# 12V_Buck_Converter.net
KiCad netlist of a schematic drawn in Altium Designer
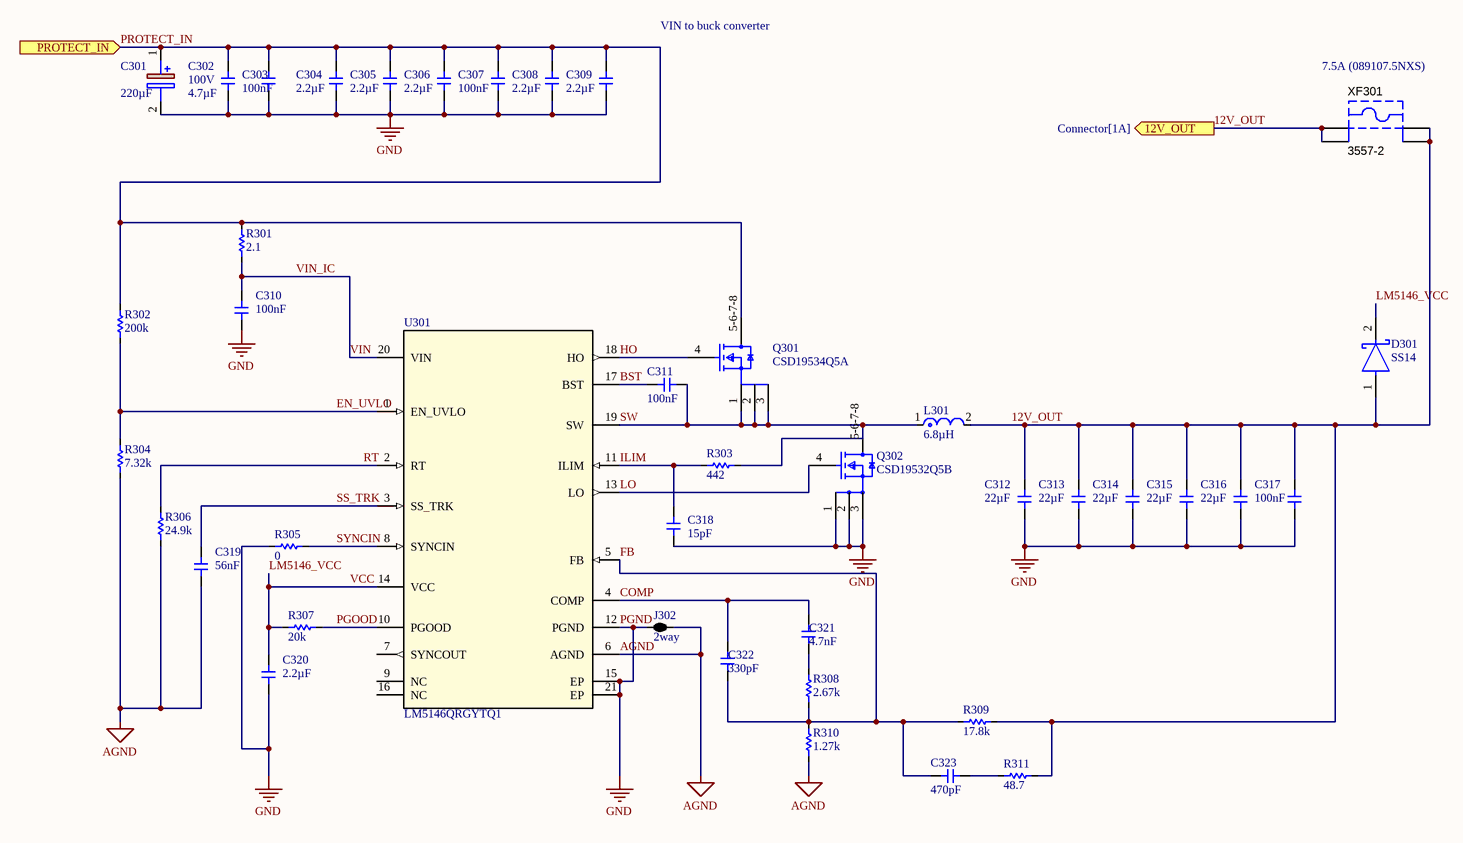
[diagram p0: 12V_Buck_Converter.SchDoc]

(export (version "E")
  (design (tool "Eeschema 10.0.6"))
  (components
    (comp (ref "C301")
      (value "220µF")
      (footprint "SamacSys:EEEFK0J103SM")
      (description "Capacitor Polarised")
      (fields
        (field (name "MANUFACTURER_PART_NUMBER") "EEV-FK2A221M")
        (field (name "MOUSER PART NUMBER") "667-EEV-FK2A221M")
      )
      (libsource (lib "*") (part "EEV-FK2A221M"))
    )
    (comp (ref "C302")
      (value "non-polar_Capacitor")
      (footprint "1210")
      (description "SMD type ceramic capacitor")
      (fields
        (field (name "VOLTAGE") "100V")
        (field (name "CAPACITANCE") "4.7µF")
        (field (name "SOURCE") "robit_passive.SchLib")
      )
      (libsource (lib "robit circuit") (part "Capacitor"))
    )
    (comp (ref "C303")
      (value "non-polar_Capacitor")
      (footprint "0603")
      (description "SMD type ceramic capacitor")
      (fields
        (field (name "VOLTAGE") "100V")
        (field (name "CAPACITANCE") "100nF")
        (field (name "SOURCE") "robit_passive.SchLib")
      )
      (libsource (lib "robit circuit") (part "Capacitor"))
    )
    (comp (ref "C304")
      (value "non-polar_Capacitor")
      (footprint "1210")
      (description "SMD type ceramic capacitor")
      (fields
        (field (name "VOLTAGE") "50V")
        (field (name "CAPACITANCE") "2.2µF")
        (field (name "SOURCE") "robit_passive.SchLib")
      )
      (libsource (lib "robit circuit") (part "Capacitor"))
    )
    (comp (ref "C305")
      (value "non-polar_Capacitor")
      (footprint "1210")
      (description "SMD type ceramic capacitor")
      (fields
        (field (name "VOLTAGE") "50V")
        (field (name "CAPACITANCE") "2.2µF")
        (field (name "SOURCE") "robit_passive.SchLib")
      )
      (libsource (lib "robit circuit") (part "Capacitor"))
    )
    (comp (ref "C306")
      (value "non-polar_Capacitor")
      (footprint "0603")
      (description "SMD type ceramic capacitor")
      (fields
        (field (name "VOLTAGE") "50V")
        (field (name "CAPACITANCE") "2.2µF")
        (field (name "SOURCE") "robit_passive.SchLib")
      )
      (libsource (lib "robit circuit") (part "Capacitor"))
    )
    (comp (ref "C307")
      (value "non-polar_Capacitor")
      (footprint "0603")
      (description "SMD type ceramic capacitor")
      (fields
        (field (name "VOLTAGE") "50V")
        (field (name "CAPACITANCE") "100nF")
        (field (name "SOURCE") "robit_passive.SchLib")
      )
      (libsource (lib "robit circuit") (part "Capacitor"))
    )
    (comp (ref "C308")
      (value "non-polar_Capacitor")
      (footprint "1210")
      (description "SMD type ceramic capacitor")
      (fields
        (field (name "VOLTAGE") "50V")
        (field (name "CAPACITANCE") "2.2µF")
        (field (name "SOURCE") "robit_passive.SchLib")
      )
      (libsource (lib "robit circuit") (part "Capacitor"))
    )
    (comp (ref "C309")
      (value "non-polar_Capacitor")
      (footprint "1210")
      (description "SMD type ceramic capacitor")
      (fields
        (field (name "VOLTAGE") "50V")
        (field (name "CAPACITANCE") "2.2µF")
        (field (name "SOURCE") "robit_passive.SchLib")
      )
      (libsource (lib "robit circuit") (part "Capacitor"))
    )
    (comp (ref "C310")
      (value "non-polar_Capacitor")
      (footprint "0603")
      (description "SMD type ceramic capacitor")
      (fields
        (field (name "VOLTAGE") "50V")
        (field (name "CAPACITANCE") "100nF")
        (field (name "SOURCE") "robit_passive.SchLib")
      )
      (libsource (lib "robit circuit") (part "Capacitor"))
    )
    (comp (ref "C311")
      (value "non-polar_Capacitor")
      (footprint "0603")
      (description "SMD type ceramic capacitor")
      (fields
        (field (name "VOLTAGE") "50V")
        (field (name "CAPACITANCE") "100nF")
        (field (name "SOURCE") "robit_passive.SchLib")
      )
      (libsource (lib "robit circuit") (part "Capacitor"))
    )
    (comp (ref "C312")
      (value "non-polar_Capacitor")
      (footprint "1210")
      (description "SMD type ceramic capacitor")
      (fields
        (field (name "VOLTAGE") "50V")
        (field (name "CAPACITANCE") "22µF")
        (field (name "SOURCE") "robit_passive.SchLib")
      )
      (libsource (lib "robit circuit") (part "Capacitor"))
    )
    (comp (ref "C313")
      (value "non-polar_Capacitor")
      (footprint "1210")
      (description "SMD type ceramic capacitor")
      (fields
        (field (name "VOLTAGE") "50V")
        (field (name "CAPACITANCE") "22µF")
        (field (name "SOURCE") "robit_passive.SchLib")
      )
      (libsource (lib "robit circuit") (part "Capacitor"))
    )
    (comp (ref "C314")
      (value "non-polar_Capacitor")
      (footprint "1210")
      (description "SMD type ceramic capacitor")
      (fields
        (field (name "VOLTAGE") "50V")
        (field (name "CAPACITANCE") "22µF")
        (field (name "SOURCE") "robit_passive.SchLib")
      )
      (libsource (lib "robit circuit") (part "Capacitor"))
    )
    (comp (ref "C315")
      (value "non-polar_Capacitor")
      (footprint "1210")
      (description "SMD type ceramic capacitor")
      (fields
        (field (name "VOLTAGE") "50V")
        (field (name "CAPACITANCE") "22µF")
        (field (name "SOURCE") "robit_passive.SchLib")
      )
      (libsource (lib "robit circuit") (part "Capacitor"))
    )
    (comp (ref "C316")
      (value "non-polar_Capacitor")
      (footprint "1210")
      (description "SMD type ceramic capacitor")
      (fields
        (field (name "VOLTAGE") "50V")
        (field (name "CAPACITANCE") "22µF")
        (field (name "SOURCE") "robit_passive.SchLib")
      )
      (libsource (lib "robit circuit") (part "Capacitor"))
    )
    (comp (ref "C317")
      (value "non-polar_Capacitor")
      (footprint "0603")
      (description "SMD type ceramic capacitor")
      (fields
        (field (name "VOLTAGE") "100V")
        (field (name "CAPACITANCE") "100nF")
        (field (name "SOURCE") "robit_passive.SchLib")
      )
      (libsource (lib "robit circuit") (part "Capacitor"))
    )
    (comp (ref "C318")
      (value "non-polar_Capacitor")
      (footprint "0603")
      (description "SMD type ceramic capacitor")
      (fields
        (field (name "VOLTAGE") "50V")
        (field (name "CAPACITANCE") "15pF")
        (field (name "SOURCE") "robit_passive.SchLib")
      )
      (libsource (lib "robit circuit") (part "Capacitor"))
    )
    (comp (ref "C319")
      (value "non-polar_Capacitor")
      (footprint "0603")
      (description "SMD type ceramic capacitor")
      (fields
        (field (name "VOLTAGE") "50V")
        (field (name "CAPACITANCE") "56nF")
        (field (name "SOURCE") "robit_passive.SchLib")
      )
      (libsource (lib "robit circuit") (part "Capacitor"))
    )
    (comp (ref "C320")
      (value "non-polar_Capacitor")
      (footprint "1206")
      (description "SMD type ceramic capacitor")
      (fields
        (field (name "VOLTAGE") "50V")
        (field (name "CAPACITANCE") "2.2µF")
        (field (name "SOURCE") "robit_passive.SchLib")
      )
      (libsource (lib "robit circuit") (part "Capacitor"))
    )
    (comp (ref "C321")
      (value "non-polar_Capacitor")
      (footprint "0603")
      (description "SMD type ceramic capacitor")
      (fields
        (field (name "VOLTAGE") "50V")
        (field (name "CAPACITANCE") "4.7nF")
        (field (name "SOURCE") "robit_passive.SchLib")
      )
      (libsource (lib "robit circuit") (part "Capacitor"))
    )
    (comp (ref "C322")
      (value "non-polar_Capacitor")
      (footprint "0603")
      (description "SMD type ceramic capacitor")
      (fields
        (field (name "VOLTAGE") "50V")
        (field (name "CAPACITANCE") "330pF")
        (field (name "SOURCE") "robit_passive.SchLib")
      )
      (libsource (lib "robit circuit") (part "Capacitor"))
    )
    (comp (ref "C323")
      (value "non-polar_Capacitor")
      (footprint "0603")
      (description "SMD type ceramic capacitor")
      (fields
        (field (name "VOLTAGE") "50V")
        (field (name "CAPACITANCE") "470pF")
        (field (name "SOURCE") "robit_passive.SchLib")
      )
      (libsource (lib "robit circuit") (part "Capacitor"))
    )
    (comp (ref "D301")
      (value "SS14")
      (footprint "FP-403AE-MFG")
      (description "DIODE SCHOTTKY 40V 1A SMA")
      (fields
        (field (name "MANUFACTURER") "ON Semiconductor")
        (field (name "OCTOPART") "https://octopart.com/ss14-on+semiconductor-29205033")
      )
      (libsource (lib "Altium Content Vault") (part "360ad2f4ac25a952324d13796385471"))
    )
    (comp (ref "J302")
      (value "2way")
      (footprint "2way_LP")
      (description "2 way net tie junction")
      (libsource (lib "robit circuit") (part "2way"))
    )
    (comp (ref "L301")
      (value "XAL1010")
      (footprint "FP-XAL1010-MFG")
      (description "General Purpose Inductor, 5.6uH, 20%, 1 Element, Composite-Core, SMD, 4539")
      (fields (field (name "INDUCTANCE") "6.8µH"))
      (libsource (lib "robit circuit") (part "4cc4b267dca4c8e51f7102f422741d8"))
    )
    (comp (ref "Q301")
      (value "CSD19534Q5A")
      (footprint "FP-DQJ0008A-MFG")
      (description "MOSFET N-CH 100V 50 8SON")
      (fields
        (field (name "OCTOPART") "https://octopart.com/csd19534q5a-texas+instruments-46749514")
        (field (name "MANUFACTURER") "Texas Instruments")
      )
      (libsource (lib "Altium Content Vault") (part "372bcbff2a0099001efc4acc0eb9b45"))
    )
    (comp (ref "Q302")
      (value "CSD19532Q5B")
      (footprint "FP-DNK0008A-MFG")
      (description "100-V, N channel NexFET™ power MOSFET, single SON 5 mm x 6 mm, 4.9 mOhm 8-VSON-CLIP -55 to 150")
      (libsource (lib "robit circuit") (part "6fb2c024a3b9031f6d89538bc87a0fd"))
    )
    (comp (ref "R301")
      (value "Resistor")
      (footprint "0603")
      (description "SMD type resistor")
      (fields (field (name "RESISTANCE") "2.1") (field (name "SOURCE") "robit_passive.SchLib"))
      (libsource (lib "robit circuit") (part "Resistor"))
    )
    (comp (ref "R302")
      (value "Resistor")
      (footprint "0603")
      (description "SMD type resistor")
      (fields (field (name "RESISTANCE") "200k") (field (name "SOURCE") "robit_passive.SchLib"))
      (libsource (lib "robit circuit") (part "Resistor"))
    )
    (comp (ref "R303")
      (value "Resistor")
      (footprint "0805")
      (description "SMD type resistor")
      (fields (field (name "RESISTANCE") "442") (field (name "SOURCE") "robit_passive.SchLib"))
      (libsource (lib "robit circuit") (part "Resistor"))
    )
    (comp (ref "R304")
      (value "Resistor")
      (footprint "0603")
      (description "SMD type resistor")
      (fields (field (name "RESISTANCE") "7.32k") (field (name "SOURCE") "robit_passive.SchLib"))
      (libsource (lib "robit circuit") (part "Resistor"))
    )
    (comp (ref "R305")
      (value "Resistor")
      (footprint "0603")
      (description "SMD type resistor")
      (fields (field (name "RESISTANCE") "0") (field (name "SOURCE") "robit_passive.SchLib"))
      (libsource (lib "robit circuit") (part "Resistor"))
    )
    (comp (ref "R306")
      (value "Resistor")
      (footprint "0603")
      (description "SMD type resistor")
      (fields (field (name "RESISTANCE") "24.9k") (field (name "SOURCE") "robit_passive.SchLib"))
      (libsource (lib "robit circuit") (part "Resistor"))
    )
    (comp (ref "R307")
      (value "Resistor")
      (footprint "0603")
      (description "SMD type resistor")
      (fields (field (name "RESISTANCE") "20k") (field (name "SOURCE") "robit_passive.SchLib"))
      (libsource (lib "robit circuit") (part "Resistor"))
    )
    (comp (ref "R308")
      (value "Resistor")
      (footprint "0603")
      (description "SMD type resistor")
      (fields (field (name "RESISTANCE") "2.67k") (field (name "SOURCE") "robit_passive.SchLib"))
      (libsource (lib "robit circuit") (part "Resistor"))
    )
    (comp (ref "R309")
      (value "Resistor")
      (footprint "0603")
      (description "SMD type resistor")
      (fields (field (name "RESISTANCE") "17.8k") (field (name "SOURCE") "robit_passive.SchLib"))
      (libsource (lib "robit circuit") (part "Resistor"))
    )
    (comp (ref "R310")
      (value "Resistor")
      (footprint "0603")
      (description "SMD type resistor")
      (fields (field (name "RESISTANCE") "1.27k") (field (name "SOURCE") "robit_passive.SchLib"))
      (libsource (lib "robit circuit") (part "Resistor"))
    )
    (comp (ref "R311")
      (value "Resistor")
      (footprint "0603")
      (description "SMD type resistor")
      (fields (field (name "RESISTANCE") "48.7") (field (name "SOURCE") "robit_passive.SchLib"))
      (libsource (lib "robit circuit") (part "Resistor"))
    )
    (comp (ref "U301")
      (value "LM5146QRGYTQ1")
      (footprint "RGY0020B")
      (description "Automotive 100-V synchronous buck DC/DC controller with wide duty-cycle range 20-VQFN -40 to 150")
      (fields (field (name "COPYRIGHT") "Copyright (C) 2026 Ultra Librarian. All rights reserved."))
      (libsource (lib "LM5146QRGYTQ1") (part "LM5146QRGYTQ1"))
    )
    (comp (ref "XF301")
      (value "3557-2")
      (footprint "KSTN-3557-2")
      (description "FUSE HOLDER, PCB MOUNT, 500VAC, 20A, ROHS")
      (fields (field (name "VOLTAGE") "500V") (field (name "MANUFACTURER") "Keystone-Electronics"))
      (libsource (lib "Altium Content Vault") (part "FUSE_HOLDER-4"))
    )
  )
  (nets
    (net (code "1") (name "/12V_OUT") (class "Default")
      (node (ref "C312") (pin "2") (pinfunction "2_2") (pintype "passive"))
      (node (ref "C313") (pin "2") (pinfunction "2_2") (pintype "passive"))
      (node (ref "C314") (pin "2") (pinfunction "2_2") (pintype "passive"))
      (node (ref "C315") (pin "2") (pinfunction "2_2") (pintype "passive"))
      (node (ref "C316") (pin "2") (pinfunction "2_2") (pintype "passive"))
      (node (ref "C317") (pin "2") (pinfunction "2_2") (pintype "passive"))
      (node (ref "D301") (pin "1") (pinfunction "A_1") (pintype "passive"))
      (node (ref "L301") (pin "2") (pinfunction "2_2") (pintype "passive"))
      (node (ref "R309") (pin "1") (pinfunction "1_1") (pintype "passive"))
      (node (ref "R311") (pin "1") (pinfunction "1_1") (pintype "passive"))
      (node (ref "XF301") (pin "1") (pinfunction "1_1") (pintype "passive"))
      (node (ref "XF301") (pin "2") (pinfunction "2_2") (pintype "passive"))
      (node (ref "XF301") (pin "3") (pinfunction "3_3") (pintype "passive"))
      (node (ref "XF301") (pin "4") (pinfunction "4_4") (pintype "passive"))
    )
    (net (code "2") (name "/BST") (class "Default")
      (node (ref "C311") (pin "2") (pinfunction "2_2") (pintype "passive"))
      (node (ref "U301") (pin "17") (pinfunction "BST_17") (pintype "passive"))
    )
    (net (code "3") (name "/COMP") (class "Default")
      (node (ref "C321") (pin "2") (pinfunction "2_2") (pintype "passive"))
      (node (ref "C322") (pin "2") (pinfunction "2_2") (pintype "passive"))
      (node (ref "U301") (pin "4") (pinfunction "COMP_4") (pintype "passive"))
    )
    (net (code "4") (name "/EN_UVLO") (class "Default")
      (node (ref "R302") (pin "1") (pinfunction "1_1") (pintype "passive"))
      (node (ref "R304") (pin "2") (pinfunction "2_2") (pintype "passive"))
      (node (ref "U301") (pin "1") (pinfunction "EN_UVLO_1") (pintype "input"))
    )
    (net (code "5") (name "/FB") (class "Default")
      (node (ref "C322") (pin "1") (pinfunction "1_1") (pintype "passive"))
      (node (ref "C323") (pin "2") (pinfunction "2_2") (pintype "passive"))
      (node (ref "R308") (pin "1") (pinfunction "1_1") (pintype "passive"))
      (node (ref "R309") (pin "2") (pinfunction "2_2") (pintype "passive"))
      (node (ref "R310") (pin "1") (pinfunction "1_1") (pintype "passive"))
      (node (ref "U301") (pin "5") (pinfunction "FB_5") (pintype "input"))
    )
    (net (code "6") (name "/HO") (class "Default")
      (node (ref "Q301") (pin "4") (pinfunction "G_4") (pintype "passive"))
      (node (ref "U301") (pin "18") (pinfunction "HO_18") (pintype "output"))
    )
    (net (code "7") (name "/ILIM") (class "Default")
      (node (ref "C318") (pin "1") (pinfunction "1_1") (pintype "passive"))
      (node (ref "R303") (pin "1") (pinfunction "1_1") (pintype "passive"))
      (node (ref "U301") (pin "11") (pinfunction "ILIM_11") (pintype "input"))
    )
    (net (code "8") (name "/LM5146_VCC") (class "Default")
      (node (ref "C320") (pin "2") (pinfunction "2_2") (pintype "passive"))
      (node (ref "D301") (pin "2") (pinfunction "C_2") (pintype "passive"))
      (node (ref "R307") (pin "2") (pinfunction "2_2") (pintype "passive"))
      (node (ref "U301") (pin "14") (pinfunction "VCC_14") (pintype "power_in"))
    )
    (net (code "9") (name "/LO") (class "Default")
      (node (ref "Q302") (pin "4") (pinfunction "G_4") (pintype "passive"))
      (node (ref "U301") (pin "13") (pinfunction "LO_13") (pintype "output"))
    )
    (net (code "10") (name "/PGOOD") (class "Default")
      (node (ref "R307") (pin "1") (pinfunction "1_1") (pintype "passive"))
      (node (ref "U301") (pin "10") (pinfunction "PGOOD_10") (pintype "open_collector"))
    )
    (net (code "11") (name "/PROTECT_IN") (class "Default")
      (node (ref "C301") (pin "1") (pinfunction "+_1") (pintype "passive"))
      (node (ref "C302") (pin "2") (pinfunction "2_2") (pintype "passive"))
      (node (ref "C303") (pin "2") (pinfunction "2_2") (pintype "passive"))
      (node (ref "C304") (pin "2") (pinfunction "2_2") (pintype "passive"))
      (node (ref "C305") (pin "2") (pinfunction "2_2") (pintype "passive"))
      (node (ref "C306") (pin "2") (pinfunction "2_2") (pintype "passive"))
      (node (ref "C307") (pin "2") (pinfunction "2_2") (pintype "passive"))
      (node (ref "C308") (pin "2") (pinfunction "2_2") (pintype "passive"))
      (node (ref "C309") (pin "2") (pinfunction "2_2") (pintype "passive"))
      (node (ref "Q301") (pin "5-6-7-8") (pinfunction "D_5-6-7-8") (pintype "passive"))
      (node (ref "R301") (pin "2") (pinfunction "2_2") (pintype "passive"))
      (node (ref "R302") (pin "2") (pinfunction "2_2") (pintype "passive"))
    )
    (net (code "12") (name "/RT") (class "Default")
      (node (ref "R306") (pin "2") (pinfunction "2_2") (pintype "passive"))
      (node (ref "U301") (pin "2") (pinfunction "RT_2") (pintype "input"))
    )
    (net (code "13") (name "/SS_TRK") (class "Default")
      (node (ref "C319") (pin "2") (pinfunction "2_2") (pintype "passive"))
      (node (ref "U301") (pin "3") (pinfunction "SS_TRK_3") (pintype "input"))
    )
    (net (code "14") (name "/SW") (class "Default")
      (node (ref "C311") (pin "1") (pinfunction "1_1") (pintype "passive"))
      (node (ref "L301") (pin "1") (pinfunction "1_1") (pintype "passive"))
      (node (ref "Q301") (pin "1") (pinfunction "S_1") (pintype "passive"))
      (node (ref "Q301") (pin "2") (pinfunction "S_2") (pintype "passive"))
      (node (ref "Q301") (pin "3") (pinfunction "S_3") (pintype "passive"))
      (node (ref "Q302") (pin "5-6-7-8") (pinfunction "D_5-6-7-8") (pintype "passive"))
      (node (ref "R303") (pin "2") (pinfunction "2_2") (pintype "passive"))
      (node (ref "U301") (pin "19") (pinfunction "SW_19") (pintype "power_in"))
    )
    (net (code "15") (name "/SYNCIN") (class "Default")
      (node (ref "R305") (pin "2") (pinfunction "2_2") (pintype "passive"))
      (node (ref "U301") (pin "8") (pinfunction "SYNCIN_8") (pintype "input"))
    )
    (net (code "16") (name "/VIN") (class "Default")
      (node (ref "C310") (pin "2") (pinfunction "2_2") (pintype "passive"))
      (node (ref "R301") (pin "1") (pinfunction "1_1") (pintype "passive"))
      (node (ref "U301") (pin "20") (pinfunction "VIN_20") (pintype "power_in"))
    )
    (net (code "17") (name "AGND") (class "Default")
      (node (ref "C319") (pin "1") (pinfunction "1_1") (pintype "passive"))
      (node (ref "J302") (pin "2") (pinfunction "2_2") (pintype "passive"))
      (node (ref "R304") (pin "1") (pinfunction "1_1") (pintype "passive"))
      (node (ref "R306") (pin "1") (pinfunction "1_1") (pintype "passive"))
      (node (ref "R310") (pin "2") (pinfunction "2_2") (pintype "passive"))
      (node (ref "U301") (pin "6") (pinfunction "AGND_6") (pintype "power_in"))
    )
    (net (code "18") (name "GND") (class "Default")
      (node (ref "C301") (pin "2") (pinfunction "-_2") (pintype "passive"))
      (node (ref "C302") (pin "1") (pinfunction "1_1") (pintype "passive"))
      (node (ref "C303") (pin "1") (pinfunction "1_1") (pintype "passive"))
      (node (ref "C304") (pin "1") (pinfunction "1_1") (pintype "passive"))
      (node (ref "C305") (pin "1") (pinfunction "1_1") (pintype "passive"))
      (node (ref "C306") (pin "1") (pinfunction "1_1") (pintype "passive"))
      (node (ref "C307") (pin "1") (pinfunction "1_1") (pintype "passive"))
      (node (ref "C308") (pin "1") (pinfunction "1_1") (pintype "passive"))
      (node (ref "C309") (pin "1") (pinfunction "1_1") (pintype "passive"))
      (node (ref "C310") (pin "1") (pinfunction "1_1") (pintype "passive"))
      (node (ref "C312") (pin "1") (pinfunction "1_1") (pintype "passive"))
      (node (ref "C313") (pin "1") (pinfunction "1_1") (pintype "passive"))
      (node (ref "C314") (pin "1") (pinfunction "1_1") (pintype "passive"))
      (node (ref "C315") (pin "1") (pinfunction "1_1") (pintype "passive"))
      (node (ref "C316") (pin "1") (pinfunction "1_1") (pintype "passive"))
      (node (ref "C317") (pin "1") (pinfunction "1_1") (pintype "passive"))
      (node (ref "C318") (pin "2") (pinfunction "2_2") (pintype "passive"))
      (node (ref "C320") (pin "1") (pinfunction "1_1") (pintype "passive"))
      (node (ref "J302") (pin "1") (pinfunction "1_1") (pintype "passive"))
      (node (ref "Q302") (pin "1") (pinfunction "S_1") (pintype "passive"))
      (node (ref "Q302") (pin "2") (pinfunction "S_2") (pintype "passive"))
      (node (ref "Q302") (pin "3") (pinfunction "S_3") (pintype "passive"))
      (node (ref "R305") (pin "1") (pinfunction "1_1") (pintype "passive"))
      (node (ref "U301") (pin "12") (pinfunction "PGND_12") (pintype "power_in"))
      (node (ref "U301") (pin "15") (pinfunction "EP_15") (pintype "power_in"))
      (node (ref "U301") (pin "21") (pinfunction "EP_21") (pintype "power_in"))
    )
    (net (code "19") (name "Net-(C321-Pad1)") (class "Default")
      (node (ref "C321") (pin "1") (pinfunction "1_1") (pintype "passive"))
      (node (ref "R308") (pin "2") (pinfunction "2_2") (pintype "passive"))
    )
    (net (code "20") (name "Net-(C323-Pad1)") (class "Default")
      (node (ref "C323") (pin "1") (pinfunction "1_1") (pintype "passive"))
      (node (ref "R311") (pin "2") (pinfunction "2_2") (pintype "passive"))
    )
    (net (code "21") (name "unconnected-(U301-NC-Pad9)") (class "Default")
      (node (ref "U301") (pin "9") (pinfunction "NC_9") (pintype "passive"))
    )
    (net (code "22") (name "unconnected-(U301-NC-Pad16)") (class "Default")
      (node (ref "U301") (pin "16") (pinfunction "NC_16") (pintype "passive"))
    )
    (net (code "23") (name "unconnected-(U301-SYNCOUT-Pad7)") (class "Default")
      (node (ref "U301") (pin "7") (pinfunction "SYNCOUT_7") (pintype "output"))
    )
  )
)
